# BM832A.net
KiCad netlist of a schematic drawn in EAGLE
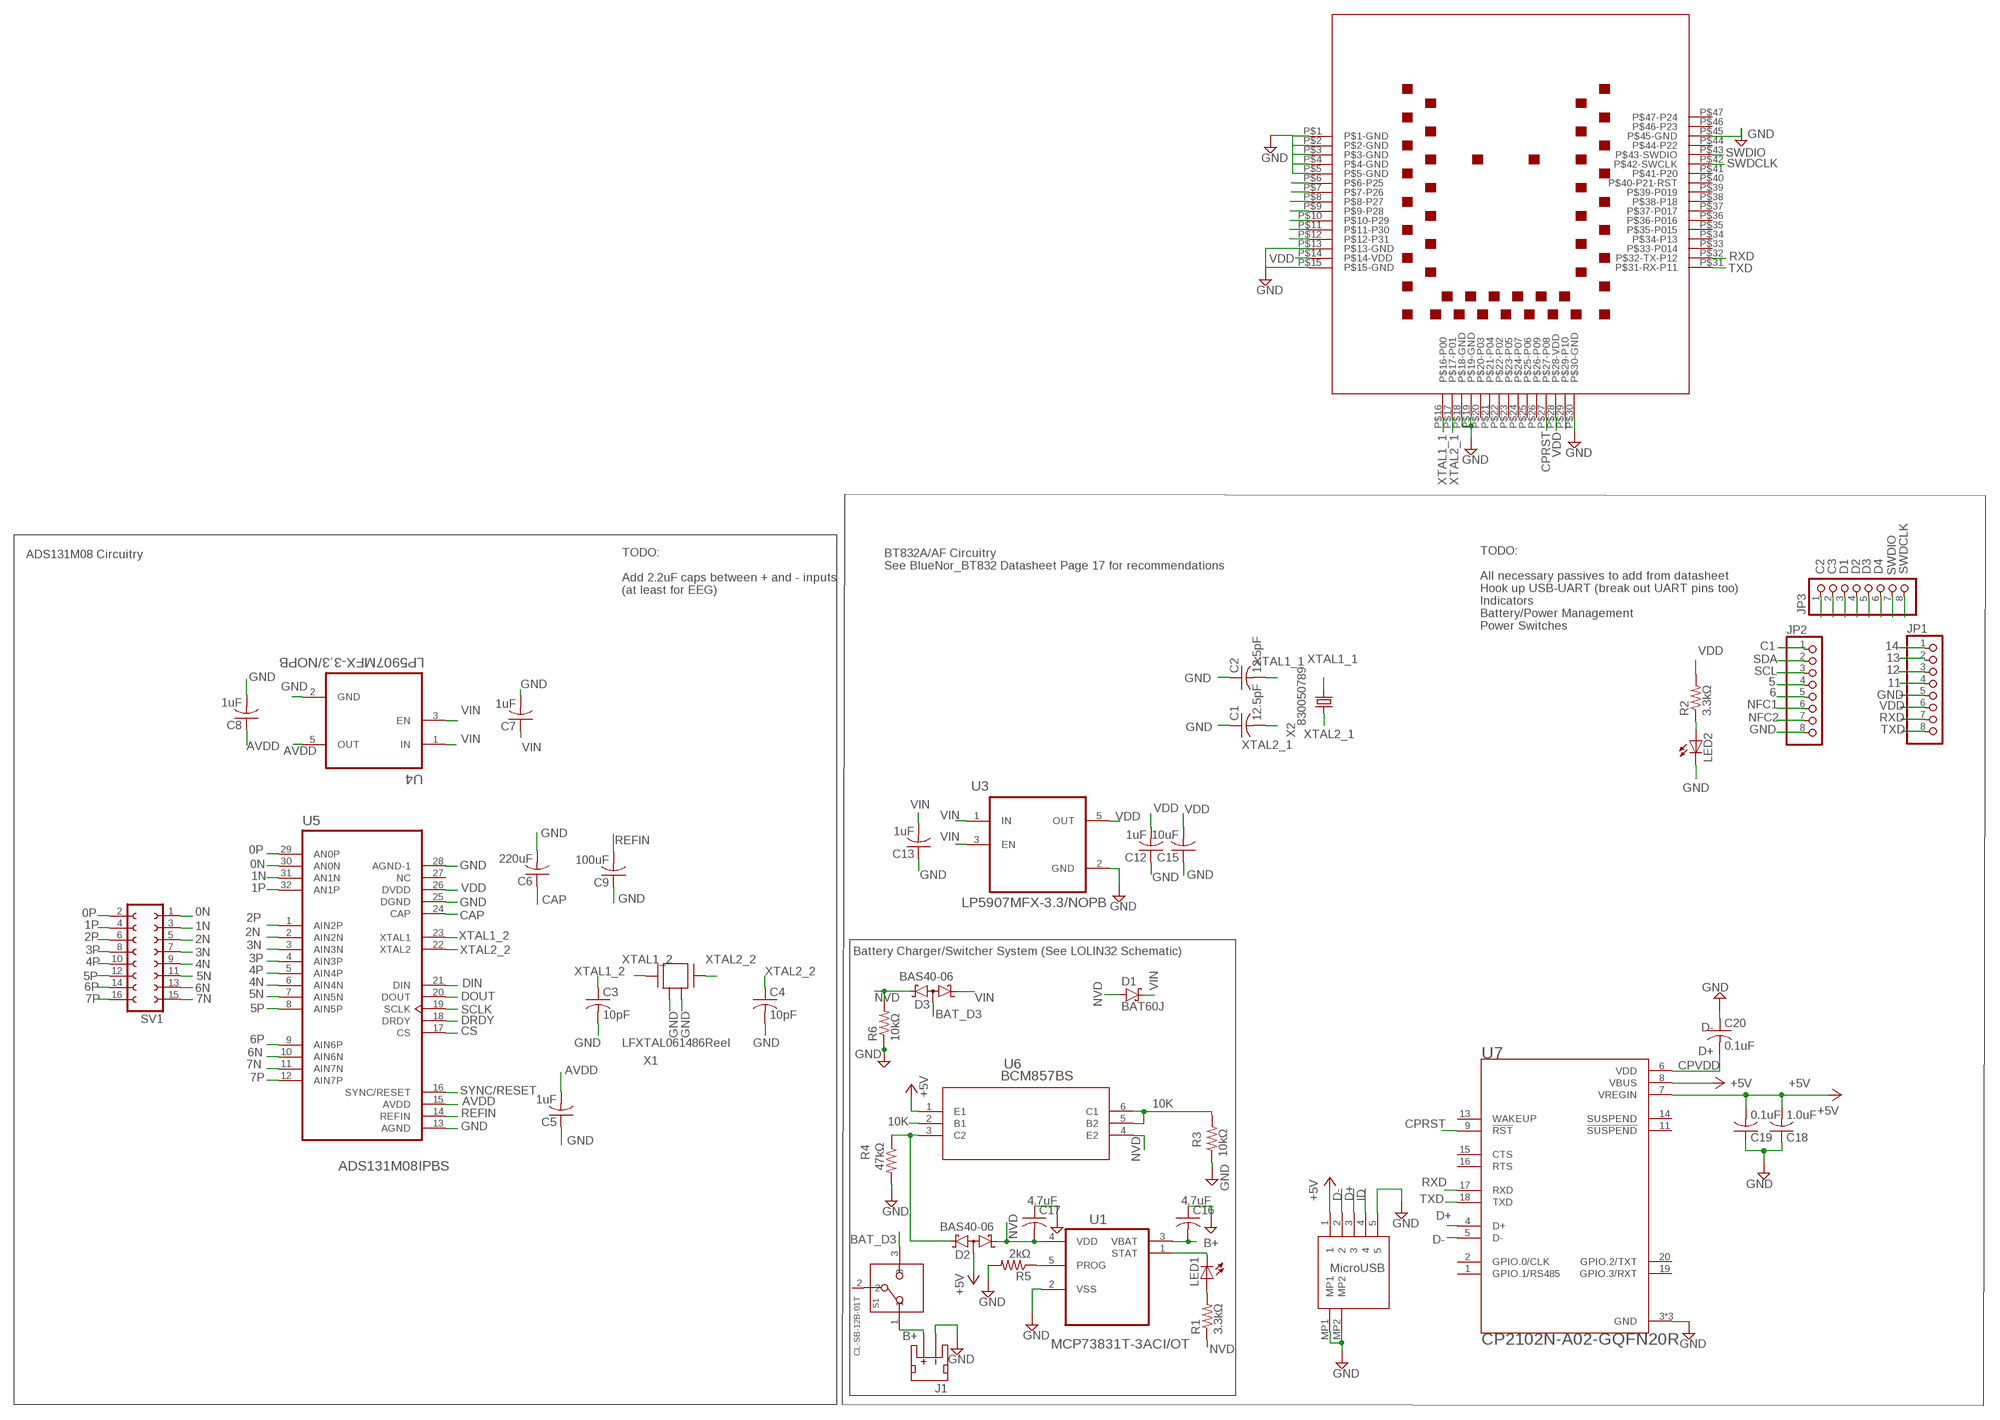
[diagram p0: schematic, sheet 1]

(export (version "E")
  (design (tool "Eeschema 10.0.6"))
  (components
    (comp (ref "C1")
      (value "12.5pF")
      (footprint "eagle-import:C0402")
      (libsource (lib "eagle-import") (part "adafruit_420_C-USC0402"))
    )
    (comp (ref "C2")
      (value "12.5pF")
      (footprint "eagle-import:C0402")
      (libsource (lib "eagle-import") (part "adafruit_420_C-USC0402"))
    )
    (comp (ref "C3")
      (value "10pF")
      (footprint "eagle-import:C0402")
      (libsource (lib "eagle-import") (part "adafruit_420_C-USC0402"))
    )
    (comp (ref "C4")
      (value "10pF")
      (footprint "eagle-import:C0402")
      (libsource (lib "eagle-import") (part "adafruit_420_C-USC0402"))
    )
    (comp (ref "C5")
      (value "1uF")
      (footprint "eagle-import:C0402")
      (libsource (lib "eagle-import") (part "C-USC0402"))
    )
    (comp (ref "C6")
      (value "220uF")
      (footprint "eagle-import:C0402")
      (libsource (lib "eagle-import") (part "C-USC0402"))
    )
    (comp (ref "C7")
      (value "1uF")
      (footprint "eagle-import:C0402")
      (libsource (lib "eagle-import") (part "C-USC0402"))
    )
    (comp (ref "C8")
      (value "1uF")
      (footprint "eagle-import:C0402")
      (libsource (lib "eagle-import") (part "C-USC0402"))
    )
    (comp (ref "C9")
      (value "100uF")
      (footprint "eagle-import:C0402")
      (libsource (lib "eagle-import") (part "C-USC0402"))
    )
    (comp (ref "C12")
      (value "1uF")
      (footprint "eagle-import:C0402")
      (libsource (lib "eagle-import") (part "C-USC0402"))
    )
    (comp (ref "C13")
      (value "1uF")
      (footprint "eagle-import:C0402")
      (libsource (lib "eagle-import") (part "C-USC0402"))
    )
    (comp (ref "C15")
      (value "10uF")
      (footprint "eagle-import:C0402")
      (libsource (lib "eagle-import") (part "C-USC0402"))
    )
    (comp (ref "C16")
      (value "4.7uF")
      (footprint "eagle-import:C0402")
      (libsource (lib "eagle-import") (part "adafruit_420_C-USC0402"))
    )
    (comp (ref "C17")
      (value "4.7uF")
      (footprint "eagle-import:C0402")
      (libsource (lib "eagle-import") (part "adafruit_420_C-USC0402"))
    )
    (comp (ref "C18")
      (value "1.0uF")
      (footprint "eagle-import:C0402")
      (libsource (lib "eagle-import") (part "adafruit_420_C-USC0402"))
    )
    (comp (ref "C19")
      (value "0.1uF")
      (footprint "eagle-import:C0402")
      (libsource (lib "eagle-import") (part "adafruit_420_C-USC0402"))
    )
    (comp (ref "C20")
      (value "0.1uF")
      (footprint "eagle-import:C0402")
      (libsource (lib "eagle-import") (part "adafruit_420_C-USC0402"))
    )
    (comp (ref "D1")
      (value "BAT60J")
      (footprint "eagle-import:SOD323_ST")
      (libsource (lib "eagle-import") (part "BAT60J"))
    )
    (comp (ref "D2")
      (value "BAS40-06")
      (footprint "eagle-import:SOT23")
      (libsource (lib "eagle-import") (part "BAS40-06"))
    )
    (comp (ref "D3")
      (value "BAS40-06")
      (footprint "eagle-import:SOT23")
      (libsource (lib "eagle-import") (part "BAS40-06"))
    )
    (comp (ref "J1")
      (value "JST_2MM_MALE")
      (footprint "eagle-import:JST-2-SMD")
      (libsource (lib "eagle-import") (part "JST_2MM_MALE"))
    )
    (comp (ref "JP1")
      (value "PINHD-1X8CLEANBIG")
      (footprint "eagle-import:1X08-CLEANBIG")
      (libsource (lib "eagle-import") (part "PINHD-1X8CLEANBIG"))
    )
    (comp (ref "JP2")
      (value "PINHD-1X8CLEANBIG")
      (footprint "eagle-import:1X08-CLEANBIG")
      (libsource (lib "eagle-import") (part "PINHD-1X8CLEANBIG"))
    )
    (comp (ref "JP3")
      (value "PINHD-1X8CLEANBIG")
      (footprint "eagle-import:1X08-CLEANBIG")
      (libsource (lib "eagle-import") (part "PINHD-1X8CLEANBIG"))
    )
    (comp (ref "LED1")
      (value "LEDCHIP-LED0603")
      (footprint "eagle-import:CHIP-LED0603")
      (libsource (lib "eagle-import") (part "LEDCHIP-LED0603"))
    )
    (comp (ref "LED2")
      (value "LEDCHIP-LED0603")
      (footprint "eagle-import:CHIP-LED0603")
      (libsource (lib "eagle-import") (part "LEDCHIP-LED0603"))
    )
    (comp (ref "R1")
      (value "3.3kΩ")
      (footprint "eagle-import:R0402")
      (libsource (lib "eagle-import") (part "R-US_R0402"))
    )
    (comp (ref "R2")
      (value "3.3kΩ")
      (footprint "eagle-import:R0402")
      (libsource (lib "eagle-import") (part "R-US_R0402"))
    )
    (comp (ref "R3")
      (value "10kΩ")
      (footprint "eagle-import:R0402")
      (libsource (lib "eagle-import") (part "R-US_R0402"))
    )
    (comp (ref "R4")
      (value "47kΩ")
      (footprint "eagle-import:R0402")
      (libsource (lib "eagle-import") (part "R-US_R0402"))
    )
    (comp (ref "R5")
      (value "2kΩ")
      (footprint "eagle-import:R0402")
      (libsource (lib "eagle-import") (part "R-US_R0402"))
    )
    (comp (ref "R6")
      (value "10kΩ")
      (footprint "eagle-import:R0402")
      (libsource (lib "eagle-import") (part "R-US_R0402"))
    )
    (comp (ref "S1")
      (value "CL-SB-12B-01T")
      (footprint "eagle-import:CL-SB-12B")
      (fields (field (name "MF") "Nidec Copal"))
      (libsource (lib "eagle-import") (part "CL-SB-12B-01T"))
    )
    (comp (ref "SV1")
      (value "FE08-2")
      (footprint "eagle-import:FE08-2")
      (libsource (lib "eagle-import") (part "FE08-2"))
    )
    (comp (ref "U$1")
      (value "DX4R005JJ2R1800")
      (footprint "eagle-import:DX4R005JJ2R1800")
      (fields (field (name "MF") "JAE Electronics"))
      (libsource (lib "eagle-import") (part "DX4R005JJ2R1800"))
    )
    (comp (ref "U1")
      (value "MCP73831T-3ACI/OT")
      (footprint "eagle-import:SOT95P270X145-5N")
      (fields (field (name "MF") "Microchip"))
      (libsource (lib "eagle-import") (part "MCP73831T-3ACI/OT"))
    )
    (comp (ref "U3")
      (value "LP5907MFX-3.3/NOPB")
      (footprint "eagle-import:SOT95P280X145-5N")
      (fields (field (name "MF") "Texas Instruments"))
      (libsource (lib "eagle-import") (part "LP5907MFX-3.3/NOPB"))
    )
    (comp (ref "U4")
      (value "LP5907MFX-3.3/NOPB")
      (footprint "eagle-import:SOT95P280X145-5N")
      (fields (field (name "MF") "Texas Instruments"))
      (libsource (lib "eagle-import") (part "LP5907MFX-3.3/NOPB"))
    )
    (comp (ref "U5")
      (value "ADS131M08IPBS")
      (footprint "eagle-import:QFP50P700X700X120-32N")
      (fields (field (name "MF") "Texas Instruments"))
      (libsource (lib "eagle-import") (part "ADS131M08IPBS"))
    )
    (comp (ref "U6")
      (value "BCM857BS")
      (footprint "eagle-import:SOT363_NEX")
      (fields (field (name "COPYRIGHT") "Copyright (C) 2016 Accelerated Designs. All rights reserved"))
      (libsource (lib "eagle-import") (part "BCM857BS"))
    )
    (comp (ref "U7")
      (value "CP2102N-A02-GQFN20R")
      (footprint "eagle-import:SILABS_CP2102N-A02-GQFN20R")
      (fields (field (name "MF") "Silicon Labs"))
      (libsource (lib "eagle-import") (part "CP2102N-A02-GQFN20R"))
    )
    (comp (ref "U8")
      (value "BM832")
      (footprint "eagle-import:BM832")
      (fields (field (name "MF") "Fanstel"))
      (libsource (lib "eagle-import") (part "BM832"))
    )
    (comp (ref "X1")
      (value "ABM3B-8.000MHZ-B2-T")
      (footprint "eagle-import:ABM3B-8.000MHZ-B2-T")
      (fields
        (field (name "DIGIKEY_PART_NUMBER") "535-9720-2-ND")
        (field (name "MANUFACTURER") "Abracon LLC")
        (field (name "CREATED_BY") "PCBLayout.com")
      )
      (libsource (lib "eagle-import") (part "ABM3B-8.000MHZ-B2-T"))
    )
    (comp (ref "X2")
      (value "FC-12M")
      (footprint "eagle-import:FC-12M")
      (libsource (lib "eagle-import") (part "FC-12M"))
    )
  )
  (nets
    (net (code "1") (name "+5V") (class "Default")
      (node (ref "C18") (pin "2") (pinfunction "2_2") (pintype "passive"))
      (node (ref "C19") (pin "2") (pinfunction "2_2") (pintype "passive"))
      (node (ref "D2") (pin "3") (pinfunction "AA_3") (pintype "passive"))
      (node (ref "U$1") (pin "1") (pinfunction "1_1") (pintype "bidirectional"))
      (node (ref "U6") (pin "1") (pinfunction "E1_1") (pintype "passive"))
      (node (ref "U7") (pin "7") (pinfunction "VREGIN_7") (pintype "power_in"))
      (node (ref "U7") (pin "8") (pinfunction "VBUS_8") (pintype "power_in"))
    )
    (net (code "2") (name "0N") (class "Default")
      (node (ref "SV1") (pin "1") (pinfunction "1_1") (pintype "passive"))
      (node (ref "U5") (pin "30") (pinfunction "AN0N_30") (pintype "bidirectional"))
    )
    (net (code "3") (name "0P") (class "Default")
      (node (ref "SV1") (pin "2") (pinfunction "2_2") (pintype "passive"))
      (node (ref "U5") (pin "29") (pinfunction "AN0P_29") (pintype "bidirectional"))
    )
    (net (code "4") (name "1N") (class "Default")
      (node (ref "SV1") (pin "3") (pinfunction "3_3") (pintype "passive"))
      (node (ref "U5") (pin "31") (pinfunction "AN1N_31") (pintype "bidirectional"))
    )
    (net (code "5") (name "1P") (class "Default")
      (node (ref "SV1") (pin "4") (pinfunction "4_4") (pintype "passive"))
      (node (ref "U5") (pin "32") (pinfunction "AN1P_32") (pintype "bidirectional"))
    )
    (net (code "6") (name "2N") (class "Default")
      (node (ref "SV1") (pin "5") (pinfunction "5_5") (pintype "passive"))
      (node (ref "U5") (pin "2") (pinfunction "AIN2N_2") (pintype "input"))
    )
    (net (code "7") (name "2P") (class "Default")
      (node (ref "SV1") (pin "6") (pinfunction "6_6") (pintype "passive"))
      (node (ref "U5") (pin "1") (pinfunction "AIN2P_1") (pintype "input"))
    )
    (net (code "8") (name "3N") (class "Default")
      (node (ref "SV1") (pin "7") (pinfunction "7_7") (pintype "passive"))
      (node (ref "U5") (pin "3") (pinfunction "AIN3N_3") (pintype "input"))
    )
    (net (code "9") (name "3P") (class "Default")
      (node (ref "SV1") (pin "8") (pinfunction "8_8") (pintype "passive"))
      (node (ref "U5") (pin "4") (pinfunction "AIN3P_4") (pintype "input"))
    )
    (net (code "10") (name "4N") (class "Default")
      (node (ref "SV1") (pin "9") (pinfunction "9_9") (pintype "passive"))
      (node (ref "U5") (pin "6") (pinfunction "AIN4N_6") (pintype "input"))
    )
    (net (code "11") (name "4P") (class "Default")
      (node (ref "SV1") (pin "10") (pinfunction "10_10") (pintype "passive"))
      (node (ref "U5") (pin "5") (pinfunction "AIN4P_5") (pintype "input"))
    )
    (net (code "12") (name "5") (class "Default")
      (node (ref "JP2") (pin "4") (pinfunction "4_4") (pintype "passive"))
    )
    (net (code "13") (name "5N") (class "Default")
      (node (ref "SV1") (pin "11") (pinfunction "11_11") (pintype "passive"))
      (node (ref "U5") (pin "7") (pinfunction "AIN5N_7") (pintype "input"))
    )
    (net (code "14") (name "5P") (class "Default")
      (node (ref "SV1") (pin "12") (pinfunction "12_12") (pintype "passive"))
      (node (ref "U5") (pin "8") (pinfunction "AIN5P_8") (pintype "input"))
    )
    (net (code "15") (name "6") (class "Default")
      (node (ref "JP2") (pin "5") (pinfunction "5_5") (pintype "passive"))
    )
    (net (code "16") (name "6N") (class "Default")
      (node (ref "SV1") (pin "13") (pinfunction "13_13") (pintype "passive"))
      (node (ref "U5") (pin "10") (pinfunction "AIN6N_10") (pintype "input"))
    )
    (net (code "17") (name "6P") (class "Default")
      (node (ref "SV1") (pin "14") (pinfunction "14_14") (pintype "passive"))
      (node (ref "U5") (pin "9") (pinfunction "AIN6P_9") (pintype "input"))
    )
    (net (code "18") (name "7N") (class "Default")
      (node (ref "SV1") (pin "15") (pinfunction "15_15") (pintype "passive"))
      (node (ref "U5") (pin "11") (pinfunction "AIN7N_11") (pintype "input"))
    )
    (net (code "19") (name "7P") (class "Default")
      (node (ref "SV1") (pin "16") (pinfunction "16_16") (pintype "passive"))
      (node (ref "U5") (pin "12") (pinfunction "AIN7P_12") (pintype "input"))
    )
    (net (code "20") (name "10K") (class "Default")
      (node (ref "R3") (pin "2") (pinfunction "2_2") (pintype "passive"))
      (node (ref "U6") (pin "2") (pinfunction "B1_2") (pintype "passive"))
      (node (ref "U6") (pin "5") (pinfunction "B2_5") (pintype "passive"))
      (node (ref "U6") (pin "6") (pinfunction "C1_6") (pintype "passive"))
    )
    (net (code "21") (name "11") (class "Default")
      (node (ref "JP1") (pin "4") (pinfunction "4_4") (pintype "passive"))
    )
    (net (code "22") (name "12") (class "Default")
      (node (ref "JP1") (pin "3") (pinfunction "3_3") (pintype "passive"))
    )
    (net (code "23") (name "13") (class "Default")
      (node (ref "JP1") (pin "2") (pinfunction "2_2") (pintype "passive"))
    )
    (net (code "24") (name "14") (class "Default")
      (node (ref "JP1") (pin "1") (pinfunction "1_1") (pintype "passive"))
    )
    (net (code "25") (name "AVDD") (class "Default")
      (node (ref "C5") (pin "2") (pinfunction "2_2") (pintype "passive"))
      (node (ref "C8") (pin "1") (pinfunction "1_1") (pintype "passive"))
      (node (ref "U4") (pin "5") (pinfunction "OUT_5") (pintype "output"))
      (node (ref "U5") (pin "15") (pinfunction "AVDD_15") (pintype "power_in"))
    )
    (net (code "26") (name "B+") (class "Default")
      (node (ref "C16") (pin "2") (pinfunction "2_2") (pintype "passive"))
      (node (ref "J1") (pin "2") (pinfunction "+_2") (pintype "bidirectional"))
      (node (ref "S1") (pin "1") (pinfunction "1_1") (pintype "bidirectional"))
      (node (ref "U1") (pin "3") (pinfunction "VBAT_3") (pintype "power_in"))
    )
    (net (code "27") (name "BAT_D3") (class "Default")
      (node (ref "D3") (pin "3") (pinfunction "AA_3") (pintype "passive"))
      (node (ref "S1") (pin "3") (pinfunction "3_3") (pintype "bidirectional"))
    )
    (net (code "28") (name "C1") (class "Default")
      (node (ref "JP2") (pin "1") (pinfunction "1_1") (pintype "passive"))
    )
    (net (code "29") (name "C2") (class "Default")
      (node (ref "JP3") (pin "1") (pinfunction "1_1") (pintype "passive"))
    )
    (net (code "30") (name "C3") (class "Default")
      (node (ref "JP3") (pin "2") (pinfunction "2_2") (pintype "passive"))
    )
    (net (code "31") (name "CAP") (class "Default")
      (node (ref "C6") (pin "1") (pinfunction "1_1") (pintype "passive"))
      (node (ref "U5") (pin "24") (pinfunction "CAP_24") (pintype "bidirectional"))
    )
    (net (code "32") (name "CPRST") (class "Default")
      (node (ref "U7") (pin "9") (pinfunction "~{RST}_9") (pintype "input"))
      (node (ref "U8") (pin "P$27") (pinfunction "P$27-P08_P$27") (pintype "bidirectional"))
    )
    (net (code "33") (name "CPVDD") (class "Default")
      (node (ref "C20") (pin "2") (pinfunction "2_2") (pintype "passive"))
      (node (ref "U7") (pin "6") (pinfunction "VDD_6") (pintype "power_in"))
    )
    (net (code "34") (name "CS") (class "Default")
      (node (ref "U5") (pin "17") (pinfunction "CS_17") (pintype "bidirectional"))
    )
    (net (code "35") (name "D+") (class "Default")
      (node (ref "U$1") (pin "3") (pinfunction "3_3") (pintype "bidirectional"))
      (node (ref "U7") (pin "4") (pinfunction "D+_4") (pintype "bidirectional"))
    )
    (net (code "36") (name "D-") (class "Default")
      (node (ref "U$1") (pin "2") (pinfunction "2_2") (pintype "bidirectional"))
      (node (ref "U7") (pin "5") (pinfunction "D-_5") (pintype "bidirectional"))
    )
    (net (code "37") (name "D1") (class "Default")
      (node (ref "JP3") (pin "3") (pinfunction "3_3") (pintype "passive"))
    )
    (net (code "38") (name "D2") (class "Default")
      (node (ref "JP3") (pin "4") (pinfunction "4_4") (pintype "passive"))
    )
    (net (code "39") (name "D3") (class "Default")
      (node (ref "JP3") (pin "5") (pinfunction "5_5") (pintype "passive"))
    )
    (net (code "40") (name "D4") (class "Default")
      (node (ref "JP3") (pin "6") (pinfunction "6_6") (pintype "passive"))
    )
    (net (code "41") (name "DIN") (class "Default")
      (node (ref "U5") (pin "21") (pinfunction "DIN_21") (pintype "input"))
    )
    (net (code "42") (name "DOUT") (class "Default")
      (node (ref "U5") (pin "20") (pinfunction "DOUT_20") (pintype "output"))
    )
    (net (code "43") (name "DRDY") (class "Default")
      (node (ref "U5") (pin "18") (pinfunction "DRDY_18") (pintype "output"))
    )
    (net (code "44") (name "GND") (class "Default")
      (node (ref "C1") (pin "1") (pinfunction "1_1") (pintype "passive"))
      (node (ref "C12") (pin "1") (pinfunction "1_1") (pintype "passive"))
      (node (ref "C13") (pin "1") (pinfunction "1_1") (pintype "passive"))
      (node (ref "C15") (pin "1") (pinfunction "1_1") (pintype "passive"))
      (node (ref "C16") (pin "1") (pinfunction "1_1") (pintype "passive"))
      (node (ref "C17") (pin "1") (pinfunction "1_1") (pintype "passive"))
      (node (ref "C18") (pin "1") (pinfunction "1_1") (pintype "passive"))
      (node (ref "C19") (pin "1") (pinfunction "1_1") (pintype "passive"))
      (node (ref "C2") (pin "1") (pinfunction "1_1") (pintype "passive"))
      (node (ref "C20") (pin "1") (pinfunction "1_1") (pintype "passive"))
      (node (ref "C3") (pin "2") (pinfunction "2_2") (pintype "passive"))
      (node (ref "C4") (pin "2") (pinfunction "2_2") (pintype "passive"))
      (node (ref "C5") (pin "1") (pinfunction "1_1") (pintype "passive"))
      (node (ref "C6") (pin "2") (pinfunction "2_2") (pintype "passive"))
      (node (ref "C7") (pin "2") (pinfunction "2_2") (pintype "passive"))
      (node (ref "C8") (pin "2") (pinfunction "2_2") (pintype "passive"))
      (node (ref "C9") (pin "1") (pinfunction "1_1") (pintype "passive"))
      (node (ref "J1") (pin "1") (pinfunction "-_1") (pintype "bidirectional"))
      (node (ref "JP1") (pin "5") (pinfunction "5_5") (pintype "passive"))
      (node (ref "JP2") (pin "8") (pinfunction "8_8") (pintype "passive"))
      (node (ref "LED2") (pin "C") (pinfunction "C_C") (pintype "passive"))
      (node (ref "R3") (pin "1") (pinfunction "1_1") (pintype "passive"))
      (node (ref "R4") (pin "2") (pinfunction "2_2") (pintype "passive"))
      (node (ref "R5") (pin "2") (pinfunction "2_2") (pintype "passive"))
      (node (ref "R6") (pin "1") (pinfunction "1_1") (pintype "passive"))
      (node (ref "U$1") (pin "5") (pinfunction "5_5") (pintype "bidirectional"))
      (node (ref "U$1") (pin "MP1") (pinfunction "MP1_MP1") (pintype "bidirectional"))
      (node (ref "U$1") (pin "MP2") (pinfunction "MP2_MP2") (pintype "bidirectional"))
      (node (ref "U1") (pin "2") (pinfunction "VSS_2") (pintype "power_in"))
      (node (ref "U3") (pin "2") (pinfunction "GND_2") (pintype "power_in"))
      (node (ref "U4") (pin "2") (pinfunction "GND_2") (pintype "power_in"))
      (node (ref "U5") (pin "13") (pinfunction "AGND_13") (pintype "power_in"))
      (node (ref "U5") (pin "25") (pinfunction "DGND_25") (pintype "power_in"))
      (node (ref "U5") (pin "28") (pinfunction "AGND-1_28") (pintype "power_in"))
      (node (ref "U7") (pin "12") (pinfunction "GND_12") (pintype "power_in"))
      (node (ref "U7") (pin "21") (pinfunction "GND_21") (pintype "power_in"))
      (node (ref "U7") (pin "3") (pinfunction "GND_3") (pintype "power_in"))
      (node (ref "U8") (pin "P$1") (pinfunction "P$1-GND_P$1") (pintype "bidirectional"))
      (node (ref "U8") (pin "P$13") (pinfunction "P$13-GND_P$13") (pintype "bidirectional"))
      (node (ref "U8") (pin "P$18") (pinfunction "P$18-GND_P$18") (pintype "bidirectional"))
      (node (ref "U8") (pin "P$19") (pinfunction "P$19-GND_P$19") (pintype "bidirectional"))
      (node (ref "U8") (pin "P$2") (pinfunction "P$2-GND_P$2") (pintype "bidirectional"))
      (node (ref "U8") (pin "P$3") (pinfunction "P$3-GND_P$3") (pintype "bidirectional"))
      (node (ref "U8") (pin "P$30") (pinfunction "P$30-GND_P$30") (pintype "bidirectional"))
      (node (ref "U8") (pin "P$4") (pinfunction "P$4-GND_P$4") (pintype "bidirectional"))
      (node (ref "U8") (pin "P$45") (pinfunction "P$45-GND_P$45") (pintype "bidirectional"))
      (node (ref "U8") (pin "P$5") (pinfunction "P$5-GND_P$5") (pintype "bidirectional"))
      (node (ref "X1") (pin "2") (pinfunction "2_2") (pintype "passive"))
      (node (ref "X1") (pin "4") (pinfunction "4_4") (pintype "passive"))
    )
    (net (code "45") (name "ID") (class "Default")
      (node (ref "U$1") (pin "4") (pinfunction "4_4") (pintype "bidirectional"))
    )
    (net (code "46") (name "NFC1") (class "Default")
      (node (ref "JP2") (pin "6") (pinfunction "6_6") (pintype "passive"))
    )
    (net (code "47") (name "NFC2") (class "Default")
      (node (ref "JP2") (pin "7") (pinfunction "7_7") (pintype "passive"))
    )
    (net (code "48") (name "NVD") (class "Default")
      (node (ref "C17") (pin "2") (pinfunction "2_2") (pintype "passive"))
      (node (ref "D1") (pin "A") (pinfunction "A_A") (pintype "passive"))
      (node (ref "D2") (pin "1") (pinfunction "K1_1") (pintype "passive"))
      (node (ref "D3") (pin "2") (pinfunction "K2_2") (pintype "passive"))
      (node (ref "R1") (pin "1") (pinfunction "1_1") (pintype "passive"))
      (node (ref "R6") (pin "2") (pinfunction "2_2") (pintype "passive"))
      (node (ref "U1") (pin "4") (pinfunction "VDD_4") (pintype "power_in"))
      (node (ref "U6") (pin "4") (pinfunction "E2_4") (pintype "passive"))
    )
    (net (code "49") (name "Net-(D2-K2)") (class "Default")
      (node (ref "D2") (pin "2") (pinfunction "K2_2") (pintype "passive"))
      (node (ref "R4") (pin "1") (pinfunction "1_1") (pintype "passive"))
      (node (ref "U6") (pin "3") (pinfunction "C2_3") (pintype "passive"))
    )
    (net (code "50") (name "Net-(LED1-PadA)") (class "Default")
      (node (ref "LED1") (pin "A") (pinfunction "A_A") (pintype "passive"))
      (node (ref "R1") (pin "2") (pinfunction "2_2") (pintype "passive"))
    )
    (net (code "51") (name "Net-(LED2-PadA)") (class "Default")
      (node (ref "LED2") (pin "A") (pinfunction "A_A") (pintype "passive"))
      (node (ref "R2") (pin "1") (pinfunction "1_1") (pintype "passive"))
    )
    (net (code "52") (name "Net-(U1-PROG)") (class "Default")
      (node (ref "R5") (pin "1") (pinfunction "1_1") (pintype "passive"))
      (node (ref "U1") (pin "5") (pinfunction "PROG_5") (pintype "input"))
    )
    (net (code "53") (name "Net-(U1-STAT)") (class "Default")
      (node (ref "LED1") (pin "C") (pinfunction "C_C") (pintype "passive"))
      (node (ref "U1") (pin "1") (pinfunction "STAT_1") (pintype "output"))
    )
    (net (code "54") (name "REFIN") (class "Default")
      (node (ref "C9") (pin "2") (pinfunction "2_2") (pintype "passive"))
      (node (ref "U5") (pin "14") (pinfunction "REFIN_14") (pintype "input"))
    )
    (net (code "55") (name "RXD") (class "Default")
      (node (ref "JP1") (pin "7") (pinfunction "7_7") (pintype "passive"))
      (node (ref "U7") (pin "17") (pinfunction "RXD_17") (pintype "input"))
      (node (ref "U8") (pin "P$32") (pinfunction "P$32-TX-P12_P$32") (pintype "bidirectional"))
    )
    (net (code "56") (name "SCL") (class "Default")
      (node (ref "JP2") (pin "3") (pinfunction "3_3") (pintype "passive"))
    )
    (net (code "57") (name "SCLK") (class "Default")
      (node (ref "U5") (pin "19") (pinfunction "SCLK_19") (pintype "input"))
    )
    (net (code "58") (name "SDA") (class "Default")
      (node (ref "JP2") (pin "2") (pinfunction "2_2") (pintype "passive"))
    )
    (net (code "59") (name "SWDCLK") (class "Default")
      (node (ref "JP3") (pin "8") (pinfunction "8_8") (pintype "passive"))
      (node (ref "U8") (pin "P$42") (pinfunction "P$42-SWCLK_P$42") (pintype "bidirectional"))
    )
    (net (code "60") (name "SWDIO") (class "Default")
      (node (ref "JP3") (pin "7") (pinfunction "7_7") (pintype "passive"))
      (node (ref "U8") (pin "P$43") (pinfunction "P$43-SWDIO_P$43") (pintype "bidirectional"))
    )
    (net (code "61") (name "SYNC{slash}RESET") (class "Default")
      (node (ref "U5") (pin "16") (pinfunction "SYNC/RESET_16") (pintype "bidirectional"))
    )
    (net (code "62") (name "TXD") (class "Default")
      (node (ref "JP1") (pin "8") (pinfunction "8_8") (pintype "passive"))
      (node (ref "U7") (pin "18") (pinfunction "TXD_18") (pintype "output"))
      (node (ref "U8") (pin "P$31") (pinfunction "P$31-RX-P11_P$31") (pintype "bidirectional"))
    )
    (net (code "63") (name "VDD") (class "Default")
      (node (ref "C12") (pin "2") (pinfunction "2_2") (pintype "passive"))
      (node (ref "C15") (pin "2") (pinfunction "2_2") (pintype "passive"))
      (node (ref "JP1") (pin "6") (pinfunction "6_6") (pintype "passive"))
      (node (ref "R2") (pin "2") (pinfunction "2_2") (pintype "passive"))
      (node (ref "U3") (pin "5") (pinfunction "OUT_5") (pintype "output"))
      (node (ref "U5") (pin "26") (pinfunction "DVDD_26") (pintype "power_in"))
      (node (ref "U8") (pin "P$14") (pinfunction "P$14-VDD_P$14") (pintype "bidirectional"))
      (node (ref "U8") (pin "P$28") (pinfunction "P$28-VDD_P$28") (pintype "bidirectional"))
    )
    (net (code "64") (name "VIN") (class "Default")
      (node (ref "C13") (pin "2") (pinfunction "2_2") (pintype "passive"))
      (node (ref "C7") (pin "1") (pinfunction "1_1") (pintype "passive"))
      (node (ref "D1") (pin "C") (pinfunction "C_C") (pintype "passive"))
      (node (ref "D3") (pin "1") (pinfunction "K1_1") (pintype "passive"))
      (node (ref "U3") (pin "1") (pinfunction "IN_1") (pintype "input"))
      (node (ref "U3") (pin "3") (pinfunction "EN_3") (pintype "input"))
      (node (ref "U4") (pin "1") (pinfunction "IN_1") (pintype "input"))
      (node (ref "U4") (pin "3") (pinfunction "EN_3") (pintype "input"))
    )
    (net (code "65") (name "XTAL1_1") (class "Default")
      (node (ref "C2") (pin "2") (pinfunction "2_2") (pintype "passive"))
      (node (ref "U8") (pin "P$16") (pinfunction "P$16-P00_P$16") (pintype "bidirectional"))
      (node (ref "X2") (pin "2") (pinfunction "2_2") (pintype "passive"))
    )
    (net (code "66") (name "XTAL1_2") (class "Default")
      (node (ref "C3") (pin "1") (pinfunction "1_1") (pintype "passive"))
      (node (ref "U5") (pin "23") (pinfunction "XTAL1_23") (pintype "bidirectional"))
      (node (ref "X1") (pin "1") (pinfunction "1_1") (pintype "passive"))
    )
    (net (code "67") (name "XTAL2_1") (class "Default")
      (node (ref "C1") (pin "2") (pinfunction "2_2") (pintype "passive"))
      (node (ref "U8") (pin "P$17") (pinfunction "P$17-P01_P$17") (pintype "bidirectional"))
      (node (ref "X2") (pin "1") (pinfunction "1_1") (pintype "passive"))
    )
    (net (code "68") (name "XTAL2_2") (class "Default")
      (node (ref "C4") (pin "1") (pinfunction "1_1") (pintype "passive"))
      (node (ref "U5") (pin "22") (pinfunction "XTAL2_22") (pintype "bidirectional"))
      (node (ref "X1") (pin "3") (pinfunction "3_3") (pintype "passive"))
    )
    (net (code "69") (name "unconnected-(J1-PAD1-PadNC1)") (class "Default")
      (node (ref "J1") (pin "NC1") (pinfunction "PAD1_NC1") (pintype "bidirectional"))
    )
    (net (code "70") (name "unconnected-(J1-PAD2-PadNC2)") (class "Default")
      (node (ref "J1") (pin "NC2") (pinfunction "PAD2_NC2") (pintype "bidirectional"))
    )
    (net (code "71") (name "unconnected-(S1-Pad2)") (class "Default")
      (node (ref "S1") (pin "2") (pinfunction "2_2") (pintype "bidirectional"))
    )
    (net (code "72") (name "unconnected-(U5-NC-Pad27)") (class "Default")
      (node (ref "U5") (pin "27") (pinfunction "NC_27") (pintype "bidirectional"))
    )
    (net (code "73") (name "unconnected-(U7-CTS-Pad15)") (class "Default")
      (node (ref "U7") (pin "15") (pinfunction "CTS_15") (pintype "input"))
    )
    (net (code "74") (name "unconnected-(U7-GPIO.0{slash}CLK-Pad2)") (class "Default")
      (node (ref "U7") (pin "2") (pinfunction "GPIO.0/CLK_2") (pintype "bidirectional"))
    )
    (net (code "75") (name "unconnected-(U7-GPIO.1{slash}RS485-Pad1)") (class "Default")
      (node (ref "U7") (pin "1") (pinfunction "GPIO.1/RS485_1") (pintype "bidirectional"))
    )
    (net (code "76") (name "unconnected-(U7-GPIO.2{slash}TXT-Pad20)") (class "Default")
      (node (ref "U7") (pin "20") (pinfunction "GPIO.2/TXT_20") (pintype "bidirectional"))
    )
    (net (code "77") (name "unconnected-(U7-GPIO.3{slash}RXT-Pad19)") (class "Default")
      (node (ref "U7") (pin "19") (pinfunction "GPIO.3/RXT_19") (pintype "bidirectional"))
    )
    (net (code "78") (name "unconnected-(U7-RTS-Pad16)") (class "Default")
      (node (ref "U7") (pin "16") (pinfunction "RTS_16") (pintype "output"))
    )
    (net (code "79") (name "unconnected-(U7-SUSPEND-Pad14)") (class "Default")
      (node (ref "U7") (pin "14") (pinfunction "SUSPEND_14") (pintype "output"))
    )
    (net (code "80") (name "unconnected-(U7-WAKEUP-Pad13)") (class "Default")
      (node (ref "U7") (pin "13") (pinfunction "WAKEUP_13") (pintype "input"))
    )
    (net (code "81") (name "unconnected-(U7-~{SUSPEND}-Pad11)") (class "Default")
      (node (ref "U7") (pin "11") (pinfunction "~{SUSPEND}_11") (pintype "output"))
    )
    (net (code "82") (name "unconnected-(U8-P$6-P25-PadP$6)") (class "Default")
      (node (ref "U8") (pin "P$6") (pinfunction "P$6-P25_P$6") (pintype "bidirectional"))
    )
    (net (code "83") (name "unconnected-(U8-P$7-P26-PadP$7)") (class "Default")
      (node (ref "U8") (pin "P$7") (pinfunction "P$7-P26_P$7") (pintype "bidirectional"))
    )
    (net (code "84") (name "unconnected-(U8-P$8-P27-PadP$8)") (class "Default")
      (node (ref "U8") (pin "P$8") (pinfunction "P$8-P27_P$8") (pintype "bidirectional"))
    )
    (net (code "85") (name "unconnected-(U8-P$9-P28-PadP$9)") (class "Default")
      (node (ref "U8") (pin "P$9") (pinfunction "P$9-P28_P$9") (pintype "bidirectional"))
    )
    (net (code "86") (name "unconnected-(U8-P$10-P29-PadP$10)") (class "Default")
      (node (ref "U8") (pin "P$10") (pinfunction "P$10-P29_P$10") (pintype "bidirectional"))
    )
    (net (code "87") (name "unconnected-(U8-P$11-P30-PadP$11)") (class "Default")
      (node (ref "U8") (pin "P$11") (pinfunction "P$11-P30_P$11") (pintype "bidirectional"))
    )
    (net (code "88") (name "unconnected-(U8-P$12-P31-PadP$12)") (class "Default")
      (node (ref "U8") (pin "P$12") (pinfunction "P$12-P31_P$12") (pintype "bidirectional"))
    )
    (net (code "89") (name "unconnected-(U8-P$15-GND-PadP$15)") (class "Default")
      (node (ref "U8") (pin "P$15") (pinfunction "P$15-GND_P$15") (pintype "bidirectional"))
    )
    (net (code "90") (name "unconnected-(U8-P$20-P03-PadP$20)") (class "Default")
      (node (ref "U8") (pin "P$20") (pinfunction "P$20-P03_P$20") (pintype "bidirectional"))
    )
    (net (code "91") (name "unconnected-(U8-P$21-P04-PadP$21)") (class "Default")
      (node (ref "U8") (pin "P$21") (pinfunction "P$21-P04_P$21") (pintype "bidirectional"))
    )
    (net (code "92") (name "unconnected-(U8-P$22-P02-PadP$22)") (class "Default")
      (node (ref "U8") (pin "P$22") (pinfunction "P$22-P02_P$22") (pintype "bidirectional"))
    )
    (net (code "93") (name "unconnected-(U8-P$23-P05-PadP$23)") (class "Default")
      (node (ref "U8") (pin "P$23") (pinfunction "P$23-P05_P$23") (pintype "bidirectional"))
    )
    (net (code "94") (name "unconnected-(U8-P$24-P07-PadP$24)") (class "Default")
      (node (ref "U8") (pin "P$24") (pinfunction "P$24-P07_P$24") (pintype "bidirectional"))
    )
    (net (code "95") (name "unconnected-(U8-P$25-P06-PadP$25)") (class "Default")
      (node (ref "U8") (pin "P$25") (pinfunction "P$25-P06_P$25") (pintype "bidirectional"))
    )
    (net (code "96") (name "unconnected-(U8-P$26-P09-PadP$26)") (class "Default")
      (node (ref "U8") (pin "P$26") (pinfunction "P$26-P09_P$26") (pintype "bidirectional"))
    )
    (net (code "97") (name "unconnected-(U8-P$29-P10-PadP$29)") (class "Default")
      (node (ref "U8") (pin "P$29") (pinfunction "P$29-P10_P$29") (pintype "bidirectional"))
    )
    (net (code "98") (name "unconnected-(U8-P$33-P014-PadP$33)") (class "Default")
      (node (ref "U8") (pin "P$33") (pinfunction "P$33-P014_P$33") (pintype "bidirectional"))
    )
    (net (code "99") (name "unconnected-(U8-P$34-P13-PadP$34)") (class "Default")
      (node (ref "U8") (pin "P$34") (pinfunction "P$34-P13_P$34") (pintype "bidirectional"))
    )
    (net (code "100") (name "unconnected-(U8-P$35-P015-PadP$35)") (class "Default")
      (node (ref "U8") (pin "P$35") (pinfunction "P$35-P015_P$35") (pintype "bidirectional"))
    )
    (net (code "101") (name "unconnected-(U8-P$36-P016-PadP$36)") (class "Default")
      (node (ref "U8") (pin "P$36") (pinfunction "P$36-P016_P$36") (pintype "bidirectional"))
    )
    (net (code "102") (name "unconnected-(U8-P$37-P017-PadP$37)") (class "Default")
      (node (ref "U8") (pin "P$37") (pinfunction "P$37-P017_P$37") (pintype "bidirectional"))
    )
    (net (code "103") (name "unconnected-(U8-P$38-P18-PadP$38)") (class "Default")
      (node (ref "U8") (pin "P$38") (pinfunction "P$38-P18_P$38") (pintype "bidirectional"))
    )
    (net (code "104") (name "unconnected-(U8-P$39-P019-PadP$39)") (class "Default")
      (node (ref "U8") (pin "P$39") (pinfunction "P$39-P019_P$39") (pintype "bidirectional"))
    )
    (net (code "105") (name "unconnected-(U8-P$40-P21-RST-PadP$40)") (class "Default")
      (node (ref "U8") (pin "P$40") (pinfunction "P$40-P21-RST_P$40") (pintype "bidirectional"))
    )
    (net (code "106") (name "unconnected-(U8-P$41-P20-PadP$41)") (class "Default")
      (node (ref "U8") (pin "P$41") (pinfunction "P$41-P20_P$41") (pintype "bidirectional"))
    )
    (net (code "107") (name "unconnected-(U8-P$44-P22-PadP$44)") (class "Default")
      (node (ref "U8") (pin "P$44") (pinfunction "P$44-P22_P$44") (pintype "bidirectional"))
    )
    (net (code "108") (name "unconnected-(U8-P$46-P23-PadP$46)") (class "Default")
      (node (ref "U8") (pin "P$46") (pinfunction "P$46-P23_P$46") (pintype "bidirectional"))
    )
    (net (code "109") (name "unconnected-(U8-P$47-P24-PadP$47)") (class "Default")
      (node (ref "U8") (pin "P$47") (pinfunction "P$47-P24_P$47") (pintype "bidirectional"))
    )
  )
)
